# DryContact.net
KiCad netlist of a schematic drawn in Altium Designer
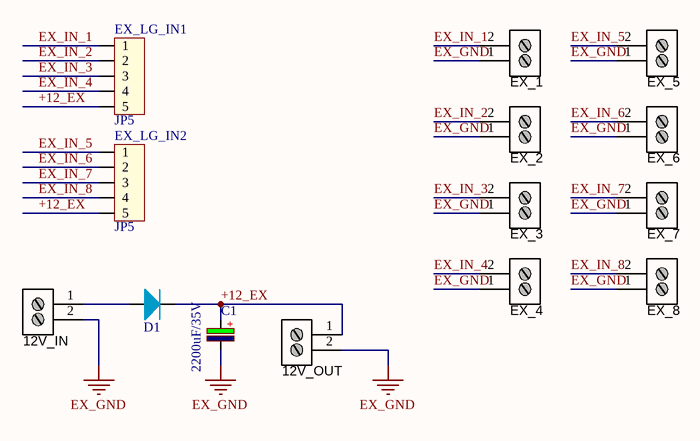
[diagram p0: DryContact.SchDoc]

(export (version "E")
  (design (tool "Eeschema 10.0.6"))
  (components
    (comp (ref "12V_IN")
      (value "Stackable ScrewTerm")
      (footprint "2P_PCB_ScrewTerm_200mil")
      (description "Terminal Block Screw Type THT 2-Position 3.81mm pitch")
      (libsource (lib "") (part "2P_ScrewTerm_90S_3.81MM_1"))
    )
    (comp (ref "12V_OUT")
      (value "Stackable ScrewTerm")
      (footprint "2P_PCB_ScrewTerm_200mil")
      (description "Terminal Block Screw Type THT 2-Position 3.81mm pitch")
      (libsource (lib "") (part "2P_ScrewTerm_90S_3.81MM_1"))
    )
    (comp (ref "C1")
      (value "2200uF/35V")
      (footprint "heromap:CP_1000uF_25V")
      (description "Cap 1000uF/16V - 220uF/50V")
      (libsource (lib "heromap") (part "CP4"))
    )
    (comp (ref "D1") (value "Diode") (footprint "Diode 3A") (libsource (lib "Tuan") (part "Diode")))
    (comp (ref "EX_1")
      (value "Stackable ScrewTerm")
      (footprint "2P_PCB_ScrewTerm_200mil")
      (description "Terminal Block Screw Type THT 2-Position 3.81mm pitch")
      (libsource (lib "PBL - Connectors") (part "2P_ScrewTerm_90S_3.81MM"))
    )
    (comp (ref "EX_2")
      (value "Stackable ScrewTerm")
      (footprint "2P_PCB_ScrewTerm_200mil")
      (description "Terminal Block Screw Type THT 2-Position 3.81mm pitch")
      (libsource (lib "PBL - Connectors") (part "2P_ScrewTerm_90S_3.81MM"))
    )
    (comp (ref "EX_3")
      (value "Stackable ScrewTerm")
      (footprint "2P_PCB_ScrewTerm_200mil")
      (description "Terminal Block Screw Type THT 2-Position 3.81mm pitch")
      (libsource (lib "PBL - Connectors") (part "2P_ScrewTerm_90S_3.81MM"))
    )
    (comp (ref "EX_4")
      (value "Stackable ScrewTerm")
      (footprint "2P_PCB_ScrewTerm_200mil")
      (description "Terminal Block Screw Type THT 2-Position 3.81mm pitch")
      (libsource (lib "PBL - Connectors") (part "2P_ScrewTerm_90S_3.81MM"))
    )
    (comp (ref "EX_5")
      (value "Stackable ScrewTerm")
      (footprint "2P_PCB_ScrewTerm_200mil")
      (description "Terminal Block Screw Type THT 2-Position 3.81mm pitch")
      (libsource (lib "PBL - Connectors") (part "2P_ScrewTerm_90S_3.81MM"))
    )
    (comp (ref "EX_6")
      (value "Stackable ScrewTerm")
      (footprint "2P_PCB_ScrewTerm_200mil")
      (description "Terminal Block Screw Type THT 2-Position 3.81mm pitch")
      (libsource (lib "PBL - Connectors") (part "2P_ScrewTerm_90S_3.81MM"))
    )
    (comp (ref "EX_7")
      (value "Stackable ScrewTerm")
      (footprint "2P_PCB_ScrewTerm_200mil")
      (description "Terminal Block Screw Type THT 2-Position 3.81mm pitch")
      (libsource (lib "PBL - Connectors") (part "2P_ScrewTerm_90S_3.81MM"))
    )
    (comp (ref "EX_8")
      (value "Stackable ScrewTerm")
      (footprint "2P_PCB_ScrewTerm_200mil")
      (description "Terminal Block Screw Type THT 2-Position 3.81mm pitch")
      (libsource (lib "PBL - Connectors") (part "2P_ScrewTerm_90S_3.81MM"))
    )
    (comp (ref "EX_LG_IN1")
      (value "JP5")
      (footprint "heromap:CON5")
      (description "Connector 5")
      (libsource (lib "heromap") (part "Con5"))
    )
    (comp (ref "EX_LG_IN2")
      (value "JP5")
      (footprint "heromap:CON5")
      (description "Connector 5")
      (libsource (lib "heromap") (part "Con5"))
    )
  )
  (nets
    (net (code "1") (name "/+12_EX") (class "Default")
      (node (ref "12V_OUT") (pin "1") (pinfunction "1_1") (pintype "passive"))
      (node (ref "C1") (pin "1") (pinfunction "1_1") (pintype "passive"))
      (node (ref "D1") (pin "2") (pinfunction "K_2") (pintype "passive"))
      (node (ref "EX_LG_IN1") (pin "5") (pinfunction "5_5") (pintype "passive"))
      (node (ref "EX_LG_IN2") (pin "5") (pinfunction "5_5") (pintype "passive"))
    )
    (net (code "2") (name "/EX_IN_1") (class "Default")
      (node (ref "EX_1") (pin "2") (pinfunction "2_2") (pintype "passive"))
      (node (ref "EX_LG_IN1") (pin "1") (pinfunction "1_1") (pintype "passive"))
    )
    (net (code "3") (name "/EX_IN_2") (class "Default")
      (node (ref "EX_2") (pin "2") (pinfunction "2_2") (pintype "passive"))
      (node (ref "EX_LG_IN1") (pin "2") (pinfunction "2_2") (pintype "passive"))
    )
    (net (code "4") (name "/EX_IN_3") (class "Default")
      (node (ref "EX_3") (pin "2") (pinfunction "2_2") (pintype "passive"))
      (node (ref "EX_LG_IN1") (pin "3") (pinfunction "3_3") (pintype "passive"))
    )
    (net (code "5") (name "/EX_IN_4") (class "Default")
      (node (ref "EX_4") (pin "2") (pinfunction "2_2") (pintype "passive"))
      (node (ref "EX_LG_IN1") (pin "4") (pinfunction "4_4") (pintype "passive"))
    )
    (net (code "6") (name "/EX_IN_5") (class "Default")
      (node (ref "EX_5") (pin "2") (pinfunction "2_2") (pintype "passive"))
      (node (ref "EX_LG_IN2") (pin "1") (pinfunction "1_1") (pintype "passive"))
    )
    (net (code "7") (name "/EX_IN_6") (class "Default")
      (node (ref "EX_6") (pin "2") (pinfunction "2_2") (pintype "passive"))
      (node (ref "EX_LG_IN2") (pin "2") (pinfunction "2_2") (pintype "passive"))
    )
    (net (code "8") (name "/EX_IN_7") (class "Default")
      (node (ref "EX_7") (pin "2") (pinfunction "2_2") (pintype "passive"))
      (node (ref "EX_LG_IN2") (pin "3") (pinfunction "3_3") (pintype "passive"))
    )
    (net (code "9") (name "/EX_IN_8") (class "Default")
      (node (ref "EX_8") (pin "2") (pinfunction "2_2") (pintype "passive"))
      (node (ref "EX_LG_IN2") (pin "4") (pinfunction "4_4") (pintype "passive"))
    )
    (net (code "10") (name "EX_GND") (class "Default")
      (node (ref "12V_IN") (pin "2") (pinfunction "2_2") (pintype "passive"))
      (node (ref "12V_OUT") (pin "2") (pinfunction "2_2") (pintype "passive"))
      (node (ref "C1") (pin "2") (pinfunction "2_2") (pintype "passive"))
      (node (ref "EX_1") (pin "1") (pinfunction "1_1") (pintype "passive"))
      (node (ref "EX_2") (pin "1") (pinfunction "1_1") (pintype "passive"))
      (node (ref "EX_3") (pin "1") (pinfunction "1_1") (pintype "passive"))
      (node (ref "EX_4") (pin "1") (pinfunction "1_1") (pintype "passive"))
      (node (ref "EX_5") (pin "1") (pinfunction "1_1") (pintype "passive"))
      (node (ref "EX_6") (pin "1") (pinfunction "1_1") (pintype "passive"))
      (node (ref "EX_7") (pin "1") (pinfunction "1_1") (pintype "passive"))
      (node (ref "EX_8") (pin "1") (pinfunction "1_1") (pintype "passive"))
    )
    (net (code "11") (name "Net-(D1-A)") (class "Default")
      (node (ref "12V_IN") (pin "1") (pinfunction "1_1") (pintype "passive"))
      (node (ref "D1") (pin "1") (pinfunction "A_1") (pintype "passive"))
    )
  )
)
